# V0_2.net
KiCad netlist of a schematic drawn in EAGLE
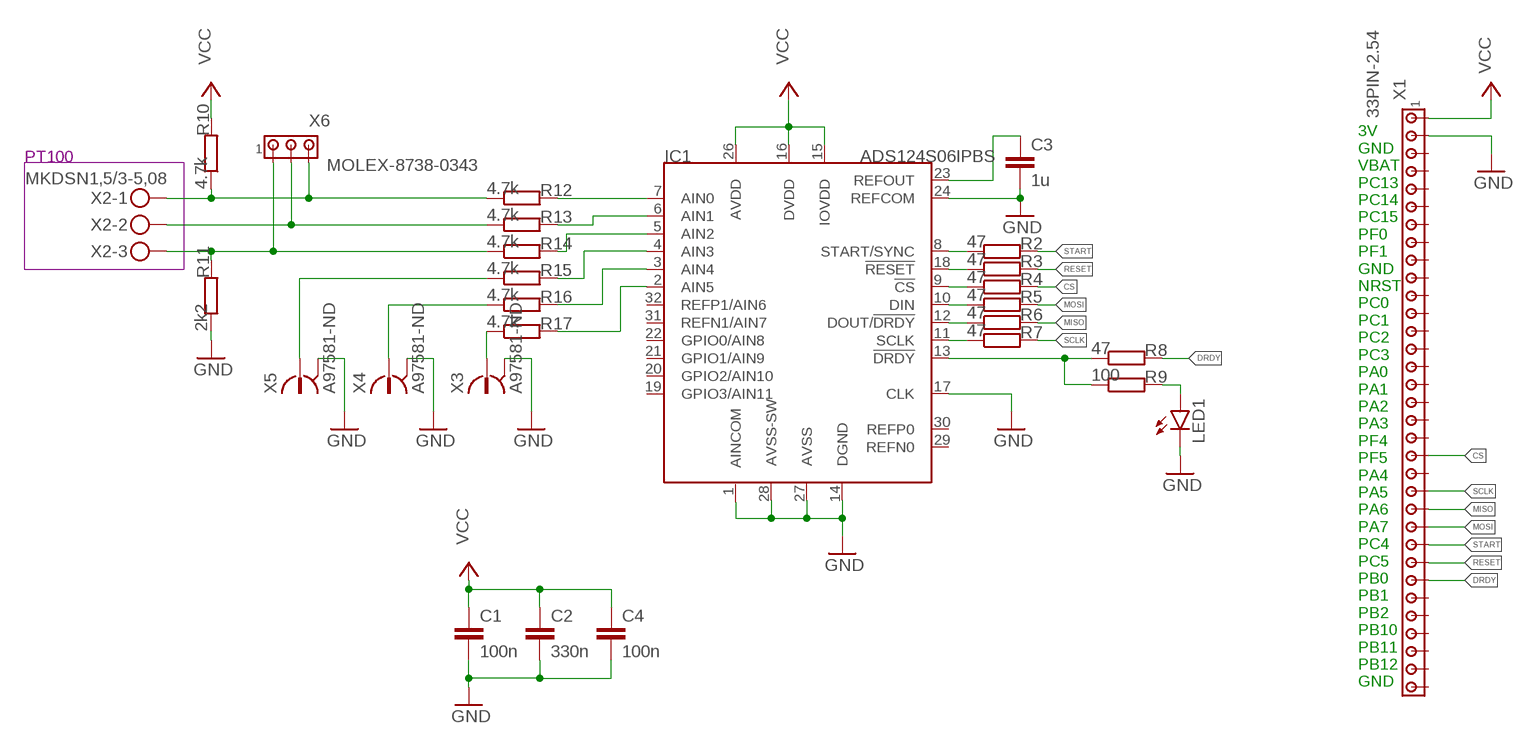
[diagram p0: schematic, sheet 1]

(export (version "E")
  (design (tool "Eeschema 10.0.6"))
  (components
    (comp (ref "C1")
      (value "100n")
      (footprint "eagle-import:C0603")
      (libsource (lib "eagle-import") (part "C-EUC0603"))
    )
    (comp (ref "C2")
      (value "330n")
      (footprint "eagle-import:C0603")
      (libsource (lib "eagle-import") (part "C-EUC0603"))
    )
    (comp (ref "C3")
      (value "1u")
      (footprint "eagle-import:C0603")
      (libsource (lib "eagle-import") (part "C-EUC0603"))
    )
    (comp (ref "C4")
      (value "100n")
      (footprint "eagle-import:C0603")
      (libsource (lib "eagle-import") (part "C-EUC0603"))
    )
    (comp (ref "IC1")
      (value "ADS124S06IPBS")
      (footprint "eagle-import:TQFP32-05")
      (libsource (lib "eagle-import") (part "ADS124S0XIPBS"))
    )
    (comp (ref "LED1")
      (value "LEDSML0603")
      (footprint "eagle-import:SML0603")
      (libsource (lib "eagle-import") (part "LEDSML0603"))
    )
    (comp (ref "R2")
      (value "47")
      (footprint "eagle-import:R0603")
      (libsource (lib "eagle-import") (part "R-EU_R0603"))
    )
    (comp (ref "R3")
      (value "47")
      (footprint "eagle-import:R0603")
      (libsource (lib "eagle-import") (part "R-EU_R0603"))
    )
    (comp (ref "R4")
      (value "47")
      (footprint "eagle-import:R0603")
      (libsource (lib "eagle-import") (part "R-EU_R0603"))
    )
    (comp (ref "R5")
      (value "47")
      (footprint "eagle-import:R0603")
      (libsource (lib "eagle-import") (part "R-EU_R0603"))
    )
    (comp (ref "R6")
      (value "47")
      (footprint "eagle-import:R0603")
      (libsource (lib "eagle-import") (part "R-EU_R0603"))
    )
    (comp (ref "R7")
      (value "47")
      (footprint "eagle-import:R0603")
      (libsource (lib "eagle-import") (part "R-EU_R0603"))
    )
    (comp (ref "R8")
      (value "47")
      (footprint "eagle-import:R0603")
      (libsource (lib "eagle-import") (part "R-EU_R0603"))
    )
    (comp (ref "R9")
      (value "100")
      (footprint "eagle-import:R0603")
      (libsource (lib "eagle-import") (part "R-EU_R0603"))
    )
    (comp (ref "R10")
      (value "4.7k")
      (footprint "eagle-import:R0603")
      (libsource (lib "eagle-import") (part "R-EU_R0603"))
    )
    (comp (ref "R11")
      (value "2k2")
      (footprint "eagle-import:R0805W")
      (libsource (lib "eagle-import") (part "R-EU_R0805W"))
    )
    (comp (ref "R12")
      (value "4.7k")
      (footprint "eagle-import:R0603")
      (libsource (lib "eagle-import") (part "R-EU_R0603"))
    )
    (comp (ref "R13")
      (value "4.7k")
      (footprint "eagle-import:R0603")
      (libsource (lib "eagle-import") (part "R-EU_R0603"))
    )
    (comp (ref "R14")
      (value "4.7k")
      (footprint "eagle-import:R0603")
      (libsource (lib "eagle-import") (part "R-EU_R0603"))
    )
    (comp (ref "R15")
      (value "4.7k")
      (footprint "eagle-import:R0603")
      (libsource (lib "eagle-import") (part "R-EU_R0603"))
    )
    (comp (ref "R16")
      (value "4.7k")
      (footprint "eagle-import:R0603")
      (libsource (lib "eagle-import") (part "R-EU_R0603"))
    )
    (comp (ref "R17")
      (value "4.7k")
      (footprint "eagle-import:R0603")
      (libsource (lib "eagle-import") (part "R-EU_R0603"))
    )
    (comp (ref "X1")
      (value "33PIN-2.54")
      (footprint "eagle-import:1X33")
      (libsource (lib "eagle-import") (part "33PIN-2.54"))
    )
    (comp (ref "X2")
      (value "MKDSN1,5/3-5,08")
      (footprint "eagle-import:MKDSN1,5_3-5,08")
      (fields (field (name "DIGIKEY_NR") "277-14503-ND") (field (name "DIGIKEY_PRICE") "1.57"))
      (libsource (lib "eagle-import") (part "MKDSN1,5/3-5,08"))
    )
    (comp (ref "X3")
      (value "A97581-ND")
      (footprint "eagle-import:1634503")
      (libsource (lib "eagle-import") (part "A97581-ND"))
    )
    (comp (ref "X4")
      (value "A97581-ND")
      (footprint "eagle-import:1634503")
      (libsource (lib "eagle-import") (part "A97581-ND"))
    )
    (comp (ref "X5")
      (value "A97581-ND")
      (footprint "eagle-import:1634503")
      (libsource (lib "eagle-import") (part "A97581-ND"))
    )
    (comp (ref "X6")
      (value "MOLEX-8738-0343")
      (footprint "eagle-import:MOLEX-87438-0343")
      (libsource (lib "eagle-import") (part "MOLEX-8738-0343"))
    )
  )
  (nets
    (net (code "1") (name "CS") (class "Default")
      (node (ref "R4") (pin "2") (pinfunction "2_2") (pintype "passive"))
      (node (ref "X1") (pin "20") (pinfunction "20_20") (pintype "passive"))
    )
    (net (code "2") (name "DRDY") (class "Default")
      (node (ref "R8") (pin "2") (pinfunction "2_2") (pintype "passive"))
      (node (ref "X1") (pin "27") (pinfunction "27_27") (pintype "passive"))
    )
    (net (code "3") (name "GND") (class "Default")
      (node (ref "C1") (pin "2") (pinfunction "2_2") (pintype "passive"))
      (node (ref "C2") (pin "2") (pinfunction "2_2") (pintype "passive"))
      (node (ref "C3") (pin "2") (pinfunction "2_2") (pintype "passive"))
      (node (ref "C4") (pin "2") (pinfunction "2_2") (pintype "passive"))
      (node (ref "IC1") (pin "1") (pinfunction "AINCOM_1") (pintype "bidirectional"))
      (node (ref "IC1") (pin "14") (pinfunction "DGND_14") (pintype "bidirectional"))
      (node (ref "IC1") (pin "17") (pinfunction "CLK_17") (pintype "bidirectional"))
      (node (ref "IC1") (pin "24") (pinfunction "REFCOM_24") (pintype "bidirectional"))
      (node (ref "IC1") (pin "27") (pinfunction "AVSS_27") (pintype "bidirectional"))
      (node (ref "IC1") (pin "28") (pinfunction "AVSS-SW_28") (pintype "bidirectional"))
      (node (ref "LED1") (pin "C") (pinfunction "C_C") (pintype "passive"))
      (node (ref "R11") (pin "1") (pinfunction "1_1") (pintype "passive"))
      (node (ref "X1") (pin "2") (pinfunction "2_2") (pintype "passive"))
      (node (ref "X3") (pin "2") (pinfunction "2_2") (pintype "passive"))
      (node (ref "X3") (pin "3") (pinfunction "2_3") (pintype "passive"))
      (node (ref "X3") (pin "4") (pinfunction "2_4") (pintype "passive"))
      (node (ref "X3") (pin "5") (pinfunction "2_5") (pintype "passive"))
      (node (ref "X4") (pin "2") (pinfunction "2_2") (pintype "passive"))
      (node (ref "X4") (pin "3") (pinfunction "2_3") (pintype "passive"))
      (node (ref "X4") (pin "4") (pinfunction "2_4") (pintype "passive"))
      (node (ref "X4") (pin "5") (pinfunction "2_5") (pintype "passive"))
      (node (ref "X5") (pin "2") (pinfunction "2_2") (pintype "passive"))
      (node (ref "X5") (pin "3") (pinfunction "2_3") (pintype "passive"))
      (node (ref "X5") (pin "4") (pinfunction "2_4") (pintype "passive"))
      (node (ref "X5") (pin "5") (pinfunction "2_5") (pintype "passive"))
    )
    (net (code "4") (name "MISO") (class "Default")
      (node (ref "R6") (pin "2") (pinfunction "2_2") (pintype "passive"))
      (node (ref "X1") (pin "23") (pinfunction "23_23") (pintype "passive"))
    )
    (net (code "5") (name "MOSI") (class "Default")
      (node (ref "R5") (pin "2") (pinfunction "2_2") (pintype "passive"))
      (node (ref "X1") (pin "24") (pinfunction "24_24") (pintype "passive"))
    )
    (net (code "6") (name "Net-(IC1-AIN0)") (class "Default")
      (node (ref "IC1") (pin "7") (pinfunction "AIN0_7") (pintype "bidirectional"))
      (node (ref "R12") (pin "2") (pinfunction "2_2") (pintype "passive"))
    )
    (net (code "7") (name "Net-(IC1-AIN1)") (class "Default")
      (node (ref "IC1") (pin "6") (pinfunction "AIN1_6") (pintype "bidirectional"))
      (node (ref "R13") (pin "2") (pinfunction "2_2") (pintype "passive"))
    )
    (net (code "8") (name "Net-(IC1-AIN2)") (class "Default")
      (node (ref "IC1") (pin "5") (pinfunction "AIN2_5") (pintype "bidirectional"))
      (node (ref "R14") (pin "2") (pinfunction "2_2") (pintype "passive"))
    )
    (net (code "9") (name "Net-(IC1-AIN3)") (class "Default")
      (node (ref "IC1") (pin "4") (pinfunction "AIN3_4") (pintype "bidirectional"))
      (node (ref "R15") (pin "2") (pinfunction "2_2") (pintype "passive"))
    )
    (net (code "10") (name "Net-(IC1-AIN4)") (class "Default")
      (node (ref "IC1") (pin "3") (pinfunction "AIN4_3") (pintype "bidirectional"))
      (node (ref "R16") (pin "2") (pinfunction "2_2") (pintype "passive"))
    )
    (net (code "11") (name "Net-(IC1-AIN5)") (class "Default")
      (node (ref "IC1") (pin "2") (pinfunction "AIN5_2") (pintype "bidirectional"))
      (node (ref "R17") (pin "2") (pinfunction "2_2") (pintype "passive"))
    )
    (net (code "12") (name "Net-(IC1-DIN)") (class "Default")
      (node (ref "IC1") (pin "10") (pinfunction "DIN_10") (pintype "bidirectional"))
      (node (ref "R5") (pin "1") (pinfunction "1_1") (pintype "passive"))
    )
    (net (code "13") (name "Net-(IC1-DOUT{slash}~{DRDY})") (class "Default")
      (node (ref "IC1") (pin "12") (pinfunction "DOUT/~{DRDY}_12") (pintype "bidirectional"))
      (node (ref "R6") (pin "1") (pinfunction "1_1") (pintype "passive"))
    )
    (net (code "14") (name "Net-(IC1-REFOUT)") (class "Default")
      (node (ref "C3") (pin "1") (pinfunction "1_1") (pintype "passive"))
      (node (ref "IC1") (pin "23") (pinfunction "REFOUT_23") (pintype "bidirectional"))
    )
    (net (code "15") (name "Net-(IC1-SCLK)") (class "Default")
      (node (ref "IC1") (pin "11") (pinfunction "SCLK_11") (pintype "bidirectional"))
      (node (ref "R7") (pin "1") (pinfunction "1_1") (pintype "passive"))
    )
    (net (code "16") (name "Net-(IC1-START{slash}SYNC)") (class "Default")
      (node (ref "IC1") (pin "8") (pinfunction "START/SYNC_8") (pintype "bidirectional"))
      (node (ref "R2") (pin "1") (pinfunction "1_1") (pintype "passive"))
    )
    (net (code "17") (name "Net-(IC1-~{CS})") (class "Default")
      (node (ref "IC1") (pin "9") (pinfunction "~{CS}_9") (pintype "bidirectional"))
      (node (ref "R4") (pin "1") (pinfunction "1_1") (pintype "passive"))
    )
    (net (code "18") (name "Net-(IC1-~{DRDY})") (class "Default")
      (node (ref "IC1") (pin "13") (pinfunction "~{DRDY}_13") (pintype "bidirectional"))
      (node (ref "R8") (pin "1") (pinfunction "1_1") (pintype "passive"))
      (node (ref "R9") (pin "1") (pinfunction "1_1") (pintype "passive"))
    )
    (net (code "19") (name "Net-(IC1-~{RESET})") (class "Default")
      (node (ref "IC1") (pin "18") (pinfunction "~{RESET}_18") (pintype "bidirectional"))
      (node (ref "R3") (pin "1") (pinfunction "1_1") (pintype "passive"))
    )
    (net (code "20") (name "Net-(LED1-PadA)") (class "Default")
      (node (ref "LED1") (pin "A") (pinfunction "A_A") (pintype "passive"))
      (node (ref "R9") (pin "2") (pinfunction "2_2") (pintype "passive"))
    )
    (net (code "21") (name "Net-(R15-Pad1)") (class "Default")
      (node (ref "R15") (pin "1") (pinfunction "1_1") (pintype "passive"))
      (node (ref "X5") (pin "1") (pinfunction "1_1") (pintype "passive"))
    )
    (net (code "22") (name "Net-(R16-Pad1)") (class "Default")
      (node (ref "R16") (pin "1") (pinfunction "1_1") (pintype "passive"))
      (node (ref "X4") (pin "1") (pinfunction "1_1") (pintype "passive"))
    )
    (net (code "23") (name "Net-(R17-Pad1)") (class "Default")
      (node (ref "R17") (pin "1") (pinfunction "1_1") (pintype "passive"))
      (node (ref "X3") (pin "1") (pinfunction "1_1") (pintype "passive"))
    )
    (net (code "24") (name "Net-(X2A-KL)") (class "Default")
      (node (ref "R10") (pin "1") (pinfunction "1_1") (pintype "passive"))
      (node (ref "R12") (pin "1") (pinfunction "1_1") (pintype "passive"))
      (node (ref "X2") (pin "1") (pinfunction "KL_1") (pintype "passive"))
      (node (ref "X6") (pin "3") (pinfunction "3_3") (pintype "passive"))
      (node (ref "X6") (pin "3_1") (pinfunction "3_3_1") (pintype "passive"))
    )
    (net (code "25") (name "Net-(X2B-KL)") (class "Default")
      (node (ref "R13") (pin "1") (pinfunction "1_1") (pintype "passive"))
      (node (ref "X2") (pin "2") (pinfunction "KL_2") (pintype "passive"))
      (node (ref "X6") (pin "2") (pinfunction "2_2") (pintype "passive"))
      (node (ref "X6") (pin "2_1") (pinfunction "2_2_1") (pintype "passive"))
    )
    (net (code "26") (name "Net-(X2C-KL)") (class "Default")
      (node (ref "R11") (pin "2") (pinfunction "2_2") (pintype "passive"))
      (node (ref "R14") (pin "1") (pinfunction "1_1") (pintype "passive"))
      (node (ref "X2") (pin "3") (pinfunction "KL_3") (pintype "passive"))
      (node (ref "X6") (pin "1") (pinfunction "1_1") (pintype "passive"))
      (node (ref "X6") (pin "1_1") (pinfunction "1_1_1") (pintype "passive"))
    )
    (net (code "27") (name "RESET") (class "Default")
      (node (ref "R3") (pin "2") (pinfunction "2_2") (pintype "passive"))
      (node (ref "X1") (pin "26") (pinfunction "26_26") (pintype "passive"))
    )
    (net (code "28") (name "SCLK") (class "Default")
      (node (ref "R7") (pin "2") (pinfunction "2_2") (pintype "passive"))
      (node (ref "X1") (pin "22") (pinfunction "22_22") (pintype "passive"))
    )
    (net (code "29") (name "START") (class "Default")
      (node (ref "R2") (pin "2") (pinfunction "2_2") (pintype "passive"))
      (node (ref "X1") (pin "25") (pinfunction "25_25") (pintype "passive"))
    )
    (net (code "30") (name "VCC") (class "Default")
      (node (ref "C1") (pin "1") (pinfunction "1_1") (pintype "passive"))
      (node (ref "C2") (pin "1") (pinfunction "1_1") (pintype "passive"))
      (node (ref "C4") (pin "1") (pinfunction "1_1") (pintype "passive"))
      (node (ref "IC1") (pin "15") (pinfunction "IOVDD_15") (pintype "bidirectional"))
      (node (ref "IC1") (pin "16") (pinfunction "DVDD_16") (pintype "bidirectional"))
      (node (ref "IC1") (pin "26") (pinfunction "AVDD_26") (pintype "bidirectional"))
      (node (ref "R10") (pin "2") (pinfunction "2_2") (pintype "passive"))
      (node (ref "X1") (pin "1") (pinfunction "1_1") (pintype "passive"))
    )
    (net (code "31") (name "unconnected-(IC1-GPIO0{slash}AIN8-Pad22)") (class "Default")
      (node (ref "IC1") (pin "22") (pinfunction "GPIO0/AIN8_22") (pintype "bidirectional"))
    )
    (net (code "32") (name "unconnected-(IC1-GPIO1{slash}AIN9-Pad21)") (class "Default")
      (node (ref "IC1") (pin "21") (pinfunction "GPIO1/AIN9_21") (pintype "bidirectional"))
    )
    (net (code "33") (name "unconnected-(IC1-GPIO2{slash}AIN10-Pad20)") (class "Default")
      (node (ref "IC1") (pin "20") (pinfunction "GPIO2/AIN10_20") (pintype "bidirectional"))
    )
    (net (code "34") (name "unconnected-(IC1-GPIO3{slash}AIN11-Pad19)") (class "Default")
      (node (ref "IC1") (pin "19") (pinfunction "GPIO3/AIN11_19") (pintype "bidirectional"))
    )
    (net (code "35") (name "unconnected-(IC1-REFN0-Pad29)") (class "Default")
      (node (ref "IC1") (pin "29") (pinfunction "REFN0_29") (pintype "bidirectional"))
    )
    (net (code "36") (name "unconnected-(IC1-REFN1{slash}AIN7-Pad31)") (class "Default")
      (node (ref "IC1") (pin "31") (pinfunction "REFN1/AIN7_31") (pintype "bidirectional"))
    )
    (net (code "37") (name "unconnected-(IC1-REFP0-Pad30)") (class "Default")
      (node (ref "IC1") (pin "30") (pinfunction "REFP0_30") (pintype "bidirectional"))
    )
    (net (code "38") (name "unconnected-(IC1-REFP1{slash}AIN6-Pad32)") (class "Default")
      (node (ref "IC1") (pin "32") (pinfunction "REFP1/AIN6_32") (pintype "bidirectional"))
    )
    (net (code "39") (name "unconnected-(X1-Pad3)") (class "Default")
      (node (ref "X1") (pin "3") (pinfunction "3_3") (pintype "passive"))
    )
    (net (code "40") (name "unconnected-(X1-Pad4)") (class "Default")
      (node (ref "X1") (pin "4") (pinfunction "4_4") (pintype "passive"))
    )
    (net (code "41") (name "unconnected-(X1-Pad5)") (class "Default")
      (node (ref "X1") (pin "5") (pinfunction "5_5") (pintype "passive"))
    )
    (net (code "42") (name "unconnected-(X1-Pad6)") (class "Default")
      (node (ref "X1") (pin "6") (pinfunction "6_6") (pintype "passive"))
    )
    (net (code "43") (name "unconnected-(X1-Pad7)") (class "Default")
      (node (ref "X1") (pin "7") (pinfunction "7_7") (pintype "passive"))
    )
    (net (code "44") (name "unconnected-(X1-Pad8)") (class "Default")
      (node (ref "X1") (pin "8") (pinfunction "8_8") (pintype "passive"))
    )
    (net (code "45") (name "unconnected-(X1-Pad9)") (class "Default")
      (node (ref "X1") (pin "9") (pinfunction "9_9") (pintype "passive"))
    )
    (net (code "46") (name "unconnected-(X1-Pad10)") (class "Default")
      (node (ref "X1") (pin "10") (pinfunction "10_10") (pintype "passive"))
    )
    (net (code "47") (name "unconnected-(X1-Pad11)") (class "Default")
      (node (ref "X1") (pin "11") (pinfunction "11_11") (pintype "passive"))
    )
    (net (code "48") (name "unconnected-(X1-Pad12)") (class "Default")
      (node (ref "X1") (pin "12") (pinfunction "12_12") (pintype "passive"))
    )
    (net (code "49") (name "unconnected-(X1-Pad13)") (class "Default")
      (node (ref "X1") (pin "13") (pinfunction "13_13") (pintype "passive"))
    )
    (net (code "50") (name "unconnected-(X1-Pad14)") (class "Default")
      (node (ref "X1") (pin "14") (pinfunction "14_14") (pintype "passive"))
    )
    (net (code "51") (name "unconnected-(X1-Pad15)") (class "Default")
      (node (ref "X1") (pin "15") (pinfunction "15_15") (pintype "passive"))
    )
    (net (code "52") (name "unconnected-(X1-Pad16)") (class "Default")
      (node (ref "X1") (pin "16") (pinfunction "16_16") (pintype "passive"))
    )
    (net (code "53") (name "unconnected-(X1-Pad17)") (class "Default")
      (node (ref "X1") (pin "17") (pinfunction "17_17") (pintype "passive"))
    )
    (net (code "54") (name "unconnected-(X1-Pad18)") (class "Default")
      (node (ref "X1") (pin "18") (pinfunction "18_18") (pintype "passive"))
    )
    (net (code "55") (name "unconnected-(X1-Pad19)") (class "Default")
      (node (ref "X1") (pin "19") (pinfunction "19_19") (pintype "passive"))
    )
    (net (code "56") (name "unconnected-(X1-Pad21)") (class "Default")
      (node (ref "X1") (pin "21") (pinfunction "21_21") (pintype "passive"))
    )
    (net (code "57") (name "unconnected-(X1-Pad28)") (class "Default")
      (node (ref "X1") (pin "28") (pinfunction "28_28") (pintype "passive"))
    )
    (net (code "58") (name "unconnected-(X1-Pad29)") (class "Default")
      (node (ref "X1") (pin "29") (pinfunction "29_29") (pintype "passive"))
    )
    (net (code "59") (name "unconnected-(X1-Pad30)") (class "Default")
      (node (ref "X1") (pin "30") (pinfunction "30_30") (pintype "passive"))
    )
    (net (code "60") (name "unconnected-(X1-Pad31)") (class "Default")
      (node (ref "X1") (pin "31") (pinfunction "31_31") (pintype "passive"))
    )
    (net (code "61") (name "unconnected-(X1-Pad32)") (class "Default")
      (node (ref "X1") (pin "32") (pinfunction "32_32") (pintype "passive"))
    )
    (net (code "62") (name "unconnected-(X1-Pad33)") (class "Default")
      (node (ref "X1") (pin "33") (pinfunction "33_33") (pintype "passive"))
    )
  )
)
